# CanTransceiver.net
KiCad netlist of a schematic drawn in Altium Designer
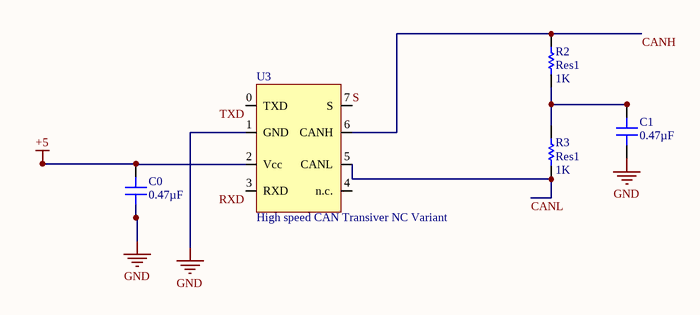
[diagram p0: CanTransceiver.SchDoc]

(export (version "E")
  (design (tool "Eeschema 10.0.6"))
  (components
    (comp (ref "C0")
      (value "0.47µF")
      (footprint "CAP 0805_2012")
      (description "CAP CER 0.47UF 16V X7R 0805 AUTO")
      (fields (field (name "PART NUMBER") "C0805X474K4RACAUTO") (field (name "MANUFACTURER") "KEMET"))
      (libsource (lib "Celestial Altium Library - altium_library") (part "Capacitor"))
    )
    (comp (ref "C1")
      (value "0.47µF")
      (footprint "CAP 0805_2012")
      (description "CAP CER 0.47UF 16V X7R 0805 AUTO")
      (fields (field (name "PART NUMBER") "C0805X474K4RACAUTO") (field (name "MANUFACTURER") "KEMET"))
      (libsource (lib "Celestial Altium Library - altium_library") (part "Capacitor"))
    )
    (comp (ref "R2")
      (value "Res1")
      (footprint "AXIAL-0.3")
      (description "Resistor")
      (fields (field (name "ALTIUM_VALUE") "1K") (field (name "PUBLISHER") "Altium Limited"))
      (libsource (lib "Miscellaneous Devices") (part "Res1"))
    )
    (comp (ref "R3")
      (value "Res1")
      (footprint "AXIAL-0.3")
      (description "Resistor")
      (fields (field (name "ALTIUM_VALUE") "1K") (field (name "PUBLISHER") "Altium Limited"))
      (libsource (lib "Miscellaneous Devices") (part "Res1"))
    )
    (comp (ref "U3")
      (value "High speed CAN Transiver NC Variant")
      (footprint "TJA1051T")
      (libsource (lib "TJA1051T") (part "TJA1051T"))
    )
  )
  (nets
    (net (code "1") (name "+5") (class "Default")
      (node (ref "C0") (pin "2") (pinfunction "2_2") (pintype "passive"))
      (node (ref "U3") (pin "2") (pinfunction "Vcc_2") (pintype "passive"))
    )
    (net (code "2") (name "/CANH") (class "Default")
      (node (ref "R2") (pin "2") (pinfunction "2_2") (pintype "passive"))
      (node (ref "U3") (pin "6") (pinfunction "CANH_6") (pintype "passive"))
    )
    (net (code "3") (name "/CANL") (class "Default")
      (node (ref "R3") (pin "1") (pinfunction "1_1") (pintype "passive"))
      (node (ref "U3") (pin "5") (pinfunction "CANL_5") (pintype "passive"))
    )
    (net (code "4") (name "/RXD") (class "Default")
      (node (ref "U3") (pin "3") (pinfunction "RXD_3") (pintype "passive"))
    )
    (net (code "5") (name "/S") (class "Default")
      (node (ref "U3") (pin "7") (pinfunction "S_7") (pintype "passive"))
    )
    (net (code "6") (name "/TXD") (class "Default")
      (node (ref "U3") (pin "0") (pinfunction "TXD_0") (pintype "passive"))
    )
    (net (code "7") (name "GND") (class "Default")
      (node (ref "C0") (pin "1") (pinfunction "1_1") (pintype "passive"))
      (node (ref "C1") (pin "1") (pinfunction "1_1") (pintype "passive"))
      (node (ref "U3") (pin "1") (pinfunction "GND_1") (pintype "passive"))
    )
    (net (code "8") (name "Net-(C1-Pad2)") (class "Default")
      (node (ref "C1") (pin "2") (pinfunction "2_2") (pintype "passive"))
      (node (ref "R2") (pin "1") (pinfunction "1_1") (pintype "passive"))
      (node (ref "R3") (pin "2") (pinfunction "2_2") (pintype "passive"))
    )
    (net (code "9") (name "unconnected-(U3-n.c.-Pad4)") (class "Default")
      (node (ref "U3") (pin "4") (pinfunction "n.c._4") (pintype "passive"))
    )
  )
)
